# rev1.net
KiCad netlist of a schematic drawn in Altium Designer
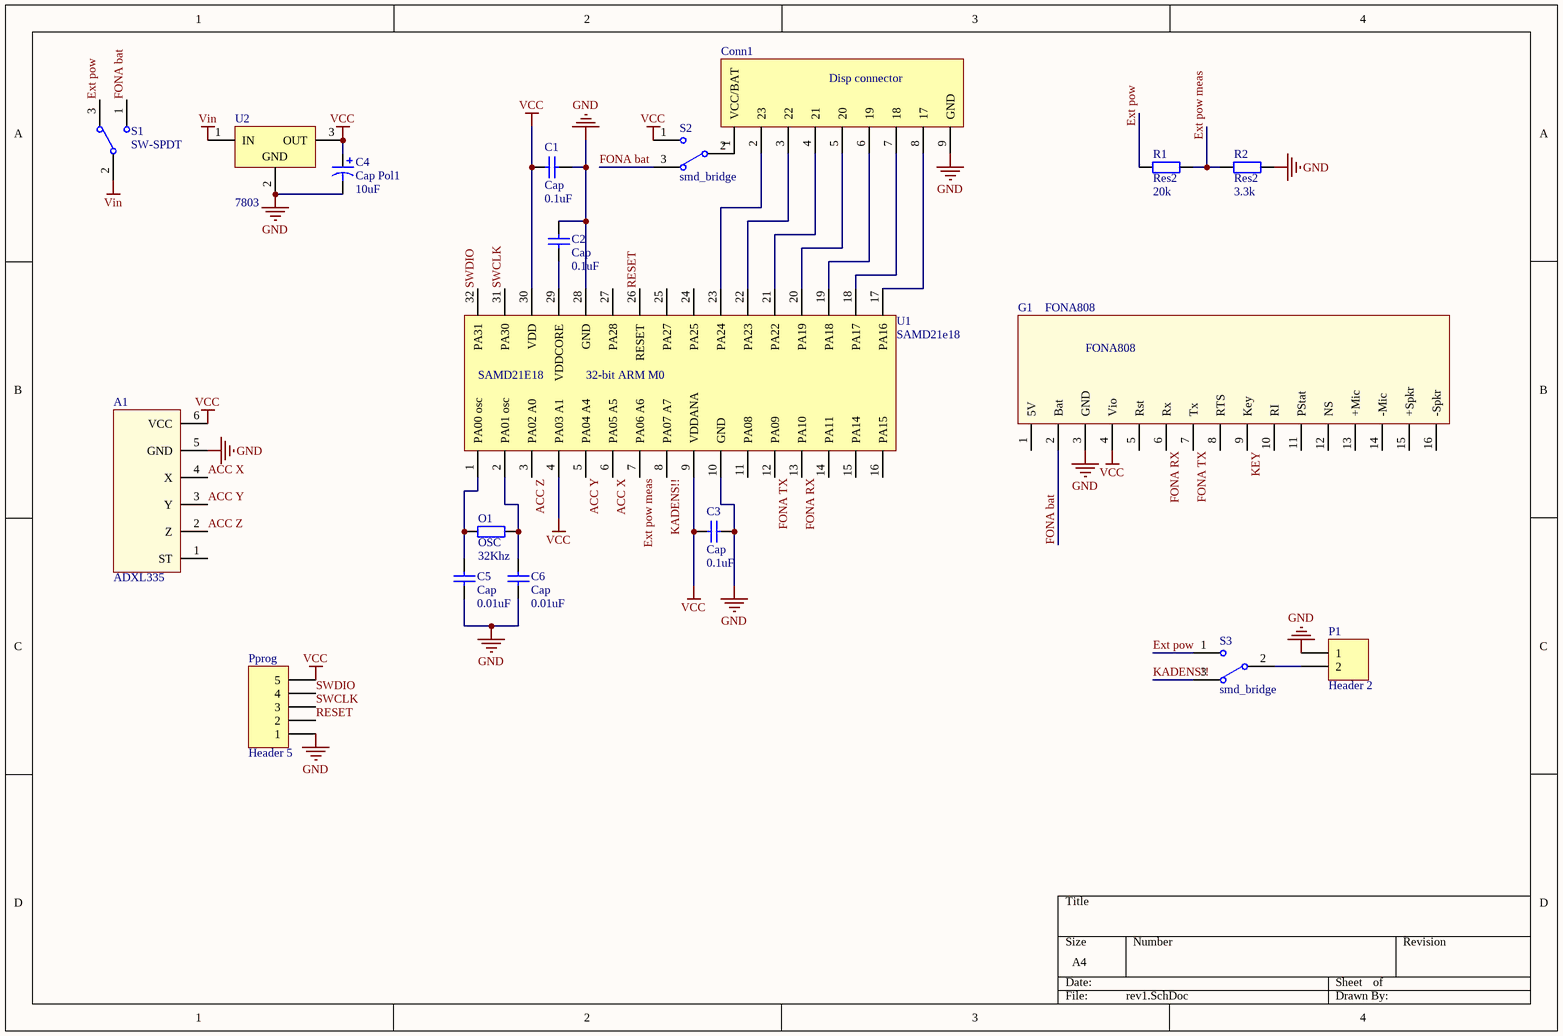
[diagram p0: rev1.SchDoc]

(export (version "E")
  (design (tool "Eeschema 10.0.6"))
  (components
    (comp (ref "A1") (value "ADXL335") (footprint "ADXL") (libsource (lib "Schlib1") (part "ADXL335")))
    (comp (ref "C1")
      (value "Cap")
      (footprint "R3216-1206")
      (description "Capacitor")
      (fields (field (name "ALTIUM_VALUE") "0.1uF") (field (name "PUBLISHER") "Altium Limited"))
      (libsource (lib "Miscellaneous Devices") (part "Cap"))
    )
    (comp (ref "C2")
      (value "Cap")
      (footprint "R3216-1206")
      (description "Capacitor")
      (fields (field (name "ALTIUM_VALUE") "0.1uF") (field (name "PUBLISHER") "Altium Limited"))
      (libsource (lib "Miscellaneous Devices") (part "Cap"))
    )
    (comp (ref "C3")
      (value "Cap")
      (footprint "R3216-1206")
      (description "Capacitor")
      (fields (field (name "ALTIUM_VALUE") "0.1uF") (field (name "PUBLISHER") "Altium Limited"))
      (libsource (lib "Miscellaneous Devices") (part "Cap"))
    )
    (comp (ref "C4")
      (value "Cap Pol1")
      (footprint "RB5-10.5")
      (description "Polarized Capacitor (Radial)")
      (fields (field (name "ALTIUM_VALUE") "10uF") (field (name "PUBLISHER") "Altium Limited"))
      (libsource (lib "Miscellaneous Devices") (part "Cap Pol1"))
    )
    (comp (ref "C5")
      (value "Cap")
      (footprint "R2012-0805")
      (description "Capacitor")
      (fields (field (name "ALTIUM_VALUE") "0.01uF") (field (name "PUBLISHER") "Altium Limited"))
      (libsource (lib "Miscellaneous Devices") (part "Cap"))
    )
    (comp (ref "C6")
      (value "Cap")
      (footprint "R2012-0805")
      (description "Capacitor")
      (fields (field (name "ALTIUM_VALUE") "0.01uF") (field (name "PUBLISHER") "Altium Limited"))
      (libsource (lib "Miscellaneous Devices") (part "Cap"))
    )
    (comp (ref "Conn1")
      (value "Disp connector")
      (footprint "9pin 2.54")
      (libsource (lib "Schlib1") (part "Disp connector"))
    )
    (comp (ref "G1") (value "FONA808") (footprint "FONA808") (libsource (lib "Schlib1") (part "FONA808")))
    (comp (ref "O1")
      (value "OSC")
      (footprint "R2012-0805")
      (description "Resistor")
      (fields (field (name "ALTIUM_VALUE") "32Khz") (field (name "PUBLISHER") "Altium Limited"))
      (libsource (lib "Miscellaneous Devices") (part "Res2"))
    )
    (comp (ref "P1")
      (value "Header 2")
      (footprint "HDR1X2")
      (description "Header, 2-Pin")
      (fields (field (name "PUBLISHER") "Altium Limited"))
      (libsource (lib "Miscellaneous Connectors") (part "Header 2"))
    )
    (comp (ref "Pprog")
      (value "Header 5")
      (footprint "HDR1X5")
      (description "Header, 5-Pin")
      (fields (field (name "PUBLISHER") "Altium Limited"))
      (libsource (lib "Miscellaneous Connectors") (part "Header 5"))
    )
    (comp (ref "R1")
      (value "Res2")
      (footprint "R2012-0805")
      (description "Resistor")
      (fields (field (name "ALTIUM_VALUE") "20k") (field (name "PUBLISHER") "Altium Limited"))
      (libsource (lib "Miscellaneous Devices") (part "Res2"))
    )
    (comp (ref "R2")
      (value "Res2")
      (footprint "R2012-0805")
      (description "Resistor")
      (fields (field (name "ALTIUM_VALUE") "3.3k") (field (name "PUBLISHER") "Altium Limited"))
      (libsource (lib "Miscellaneous Devices") (part "Res2"))
    )
    (comp (ref "S1")
      (value "SW-SPDT")
      (footprint "SW-SPDT2.54mm")
      (description "SPDT Subminiature Toggle Switch, Right Angle Mounting, Vertical Actuation")
      (fields (field (name "PUBLISHER") "Altium Limited"))
      (libsource (lib "Schlib1") (part "SW-SPDT"))
    )
    (comp (ref "S2")
      (value "smd_bridge")
      (footprint "SMD_BRIDGE")
      (libsource (lib "Schlib1") (part "smd_bridge"))
    )
    (comp (ref "S3")
      (value "smd_bridge")
      (footprint "SMD_BRIDGE")
      (libsource (lib "Schlib1") (part "smd_bridge"))
    )
    (comp (ref "U1")
      (value "SAMD21e18")
      (footprint "TQFP32_N")
      (libsource (lib "Schlib1") (part "SAMD21e18"))
    )
    (comp (ref "U2")
      (value "7803")
      (footprint "221A-04")
      (description "3-Terminal Positive Fixed Voltage Regulator")
      (fields (field (name "PUBLISHER") "Altium Limited"))
      (libsource (lib "Schlib1") (part "7803"))
    )
  )
  (nets
    (net (code "1") (name "/ACC X") (class "Default")
      (node (ref "A1") (pin "4") (pinfunction "X_4") (pintype "passive"))
      (node (ref "U1") (pin "6") (pinfunction "PA05_A5_6") (pintype "passive"))
    )
    (net (code "2") (name "/ACC Y") (class "Default")
      (node (ref "A1") (pin "3") (pinfunction "Y_3") (pintype "passive"))
      (node (ref "U1") (pin "5") (pinfunction "PA04_A4_5") (pintype "passive"))
    )
    (net (code "3") (name "/ACC Z") (class "Default")
      (node (ref "A1") (pin "2") (pinfunction "Z_2") (pintype "passive"))
      (node (ref "U1") (pin "3") (pinfunction "PA02_A0_3") (pintype "passive"))
    )
    (net (code "4") (name "/Ext pow") (class "Default")
      (node (ref "R1") (pin "1") (pinfunction "1_1") (pintype "passive"))
      (node (ref "S1") (pin "3") (pinfunction "3_3") (pintype "passive"))
      (node (ref "S3") (pin "1") (pinfunction "1_1") (pintype "passive"))
    )
    (net (code "5") (name "/Ext pow meas") (class "Default")
      (node (ref "R1") (pin "2") (pinfunction "2_2") (pintype "passive"))
      (node (ref "R2") (pin "1") (pinfunction "1_1") (pintype "passive"))
      (node (ref "U1") (pin "7") (pinfunction "PA06_A6_7") (pintype "passive"))
    )
    (net (code "6") (name "/FONA RX") (class "Default")
      (node (ref "G1") (pin "6") (pinfunction "Rx_6") (pintype "passive"))
      (node (ref "U1") (pin "13") (pinfunction "PA10_13") (pintype "passive"))
    )
    (net (code "7") (name "/FONA TX") (class "Default")
      (node (ref "G1") (pin "7") (pinfunction "Tx_7") (pintype "passive"))
      (node (ref "U1") (pin "12") (pinfunction "PA09_12") (pintype "passive"))
    )
    (net (code "8") (name "/FONA bat") (class "Default")
      (node (ref "G1") (pin "2") (pinfunction "Bat_2") (pintype "passive"))
      (node (ref "S1") (pin "1") (pinfunction "1_1") (pintype "passive"))
      (node (ref "S2") (pin "3") (pinfunction "3_3") (pintype "passive"))
    )
    (net (code "9") (name "/KADENS!!") (class "Default")
      (node (ref "S3") (pin "3") (pinfunction "3_3") (pintype "passive"))
      (node (ref "U1") (pin "8") (pinfunction "PA07_A7_8") (pintype "passive"))
    )
    (net (code "10") (name "/KEY") (class "Default")
      (node (ref "G1") (pin "9") (pinfunction "Key_9") (pintype "passive"))
    )
    (net (code "11") (name "/RESET") (class "Default")
      (node (ref "Pprog") (pin "2") (pinfunction "2_2") (pintype "passive"))
      (node (ref "U1") (pin "26") (pinfunction "RESET_26") (pintype "passive"))
    )
    (net (code "12") (name "/SWCLK") (class "Default")
      (node (ref "Pprog") (pin "3") (pinfunction "3_3") (pintype "passive"))
      (node (ref "U1") (pin "31") (pinfunction "PA30_31") (pintype "passive"))
    )
    (net (code "13") (name "/SWDIO") (class "Default")
      (node (ref "Pprog") (pin "4") (pinfunction "4_4") (pintype "passive"))
      (node (ref "U1") (pin "32") (pinfunction "PA31_32") (pintype "passive"))
    )
    (net (code "14") (name "GND") (class "Default")
      (node (ref "A1") (pin "5") (pinfunction "GND_5") (pintype "passive"))
      (node (ref "C1") (pin "1") (pinfunction "1_1") (pintype "passive"))
      (node (ref "C2") (pin "2") (pinfunction "2_2") (pintype "passive"))
      (node (ref "C3") (pin "1") (pinfunction "1_1") (pintype "passive"))
      (node (ref "C4") (pin "2") (pinfunction "2_2") (pintype "passive"))
      (node (ref "C5") (pin "1") (pinfunction "1_1") (pintype "passive"))
      (node (ref "C6") (pin "1") (pinfunction "1_1") (pintype "passive"))
      (node (ref "Conn1") (pin "9") (pinfunction "GND_9") (pintype "passive"))
      (node (ref "G1") (pin "3") (pinfunction "GND_3") (pintype "passive"))
      (node (ref "P1") (pin "1") (pinfunction "1_1") (pintype "passive"))
      (node (ref "Pprog") (pin "1") (pinfunction "1_1") (pintype "passive"))
      (node (ref "R2") (pin "2") (pinfunction "2_2") (pintype "passive"))
      (node (ref "U1") (pin "10") (pinfunction "GND_10") (pintype "passive"))
      (node (ref "U1") (pin "28") (pinfunction "GND_28") (pintype "passive"))
      (node (ref "U2") (pin "2") (pinfunction "GND_2") (pintype "power_in"))
    )
    (net (code "15") (name "Net-(Conn1-17)") (class "Default")
      (node (ref "Conn1") (pin "8") (pinfunction "17_8") (pintype "passive"))
      (node (ref "U1") (pin "17") (pinfunction "PA16_17") (pintype "passive"))
    )
    (net (code "16") (name "Net-(Conn1-18)") (class "Default")
      (node (ref "Conn1") (pin "7") (pinfunction "18_7") (pintype "passive"))
      (node (ref "U1") (pin "18") (pinfunction "PA17_18") (pintype "passive"))
    )
    (net (code "17") (name "Net-(Conn1-19)") (class "Default")
      (node (ref "Conn1") (pin "6") (pinfunction "19_6") (pintype "passive"))
      (node (ref "U1") (pin "19") (pinfunction "PA18_19") (pintype "passive"))
    )
    (net (code "18") (name "Net-(Conn1-20)") (class "Default")
      (node (ref "Conn1") (pin "5") (pinfunction "20_5") (pintype "passive"))
      (node (ref "U1") (pin "20") (pinfunction "PA19_20") (pintype "passive"))
    )
    (net (code "19") (name "Net-(Conn1-21)") (class "Default")
      (node (ref "Conn1") (pin "4") (pinfunction "21_4") (pintype "passive"))
      (node (ref "U1") (pin "21") (pinfunction "PA22_21") (pintype "passive"))
    )
    (net (code "20") (name "Net-(Conn1-22)") (class "Default")
      (node (ref "Conn1") (pin "3") (pinfunction "22_3") (pintype "passive"))
      (node (ref "U1") (pin "22") (pinfunction "PA23_22") (pintype "passive"))
    )
    (net (code "21") (name "Net-(Conn1-23)") (class "Default")
      (node (ref "Conn1") (pin "2") (pinfunction "23_2") (pintype "passive"))
      (node (ref "U1") (pin "23") (pinfunction "PA24_23") (pintype "passive"))
    )
    (net (code "22") (name "Net-(Conn1-VCC{slash}BAT)") (class "Default")
      (node (ref "Conn1") (pin "1") (pinfunction "VCC/BAT_1") (pintype "passive"))
      (node (ref "S2") (pin "2") (pinfunction "2_2") (pintype "passive"))
    )
    (net (code "23") (name "Net-(P1-Pad2)") (class "Default")
      (node (ref "P1") (pin "2") (pinfunction "2_2") (pintype "passive"))
      (node (ref "S3") (pin "2") (pinfunction "2_2") (pintype "passive"))
    )
    (net (code "24") (name "Net-(U1-PA00_osc)") (class "Default")
      (node (ref "C5") (pin "2") (pinfunction "2_2") (pintype "passive"))
      (node (ref "O1") (pin "1") (pinfunction "1_1") (pintype "passive"))
      (node (ref "U1") (pin "1") (pinfunction "PA00_osc_1") (pintype "passive"))
    )
    (net (code "25") (name "Net-(U1-PA01_osc)") (class "Default")
      (node (ref "C6") (pin "2") (pinfunction "2_2") (pintype "passive"))
      (node (ref "O1") (pin "2") (pinfunction "2_2") (pintype "passive"))
      (node (ref "U1") (pin "2") (pinfunction "PA01_osc_2") (pintype "passive"))
    )
    (net (code "26") (name "Net-(U1-VDDCORE)") (class "Default")
      (node (ref "C2") (pin "1") (pinfunction "1_1") (pintype "passive"))
      (node (ref "U1") (pin "29") (pinfunction "VDDCORE_29") (pintype "passive"))
    )
    (net (code "27") (name "VCC") (class "Default")
      (node (ref "A1") (pin "6") (pinfunction "VCC_6") (pintype "passive"))
      (node (ref "C1") (pin "2") (pinfunction "2_2") (pintype "passive"))
      (node (ref "C3") (pin "2") (pinfunction "2_2") (pintype "passive"))
      (node (ref "C4") (pin "1") (pinfunction "1_1") (pintype "passive"))
      (node (ref "G1") (pin "4") (pinfunction "Vio_4") (pintype "passive"))
      (node (ref "Pprog") (pin "5") (pinfunction "5_5") (pintype "passive"))
      (node (ref "S2") (pin "1") (pinfunction "1_1") (pintype "passive"))
      (node (ref "U1") (pin "30") (pinfunction "VDD_30") (pintype "passive"))
      (node (ref "U1") (pin "4") (pinfunction "PA03_A1_4") (pintype "passive"))
      (node (ref "U1") (pin "9") (pinfunction "VDDANA_9") (pintype "passive"))
      (node (ref "U2") (pin "3") (pinfunction "OUT_3") (pintype "power_in"))
    )
    (net (code "28") (name "Vin") (class "Default")
      (node (ref "S1") (pin "2") (pinfunction "2_2") (pintype "passive"))
      (node (ref "U2") (pin "1") (pinfunction "IN_1") (pintype "power_in"))
    )
    (net (code "29") (name "unconnected-(A1-ST-Pad1)") (class "Default")
      (node (ref "A1") (pin "1") (pinfunction "ST_1") (pintype "passive"))
    )
    (net (code "30") (name "unconnected-(G1-+Mic-Pad13)") (class "Default")
      (node (ref "G1") (pin "13") (pinfunction "+Mic_13") (pintype "passive"))
    )
    (net (code "31") (name "unconnected-(G1-+Spkr-Pad15)") (class "Default")
      (node (ref "G1") (pin "15") (pinfunction "+Spkr_15") (pintype "passive"))
    )
    (net (code "32") (name "unconnected-(G1--Mic-Pad14)") (class "Default")
      (node (ref "G1") (pin "14") (pinfunction "-Mic_14") (pintype "passive"))
    )
    (net (code "33") (name "unconnected-(G1--Spkr-Pad16)") (class "Default")
      (node (ref "G1") (pin "16") (pinfunction "-Spkr_16") (pintype "passive"))
    )
    (net (code "34") (name "unconnected-(G1-5V-Pad1)") (class "Default")
      (node (ref "G1") (pin "1") (pinfunction "5V_1") (pintype "passive"))
    )
    (net (code "35") (name "unconnected-(G1-NS-Pad12)") (class "Default")
      (node (ref "G1") (pin "12") (pinfunction "NS_12") (pintype "passive"))
    )
    (net (code "36") (name "unconnected-(G1-PStat-Pad11)") (class "Default")
      (node (ref "G1") (pin "11") (pinfunction "PStat_11") (pintype "passive"))
    )
    (net (code "37") (name "unconnected-(G1-RI-Pad10)") (class "Default")
      (node (ref "G1") (pin "10") (pinfunction "RI_10") (pintype "passive"))
    )
    (net (code "38") (name "unconnected-(G1-RTS-Pad8)") (class "Default")
      (node (ref "G1") (pin "8") (pinfunction "RTS_8") (pintype "passive"))
    )
    (net (code "39") (name "unconnected-(G1-Rst-Pad5)") (class "Default")
      (node (ref "G1") (pin "5") (pinfunction "Rst_5") (pintype "passive"))
    )
    (net (code "40") (name "unconnected-(U1-PA08-Pad11)") (class "Default")
      (node (ref "U1") (pin "11") (pinfunction "PA08_11") (pintype "passive"))
    )
    (net (code "41") (name "unconnected-(U1-PA11-Pad14)") (class "Default")
      (node (ref "U1") (pin "14") (pinfunction "PA11_14") (pintype "passive"))
    )
    (net (code "42") (name "unconnected-(U1-PA14-Pad15)") (class "Default")
      (node (ref "U1") (pin "15") (pinfunction "PA14_15") (pintype "passive"))
    )
    (net (code "43") (name "unconnected-(U1-PA15-Pad16)") (class "Default")
      (node (ref "U1") (pin "16") (pinfunction "PA15_16") (pintype "passive"))
    )
    (net (code "44") (name "unconnected-(U1-PA25-Pad24)") (class "Default")
      (node (ref "U1") (pin "24") (pinfunction "PA25_24") (pintype "passive"))
    )
    (net (code "45") (name "unconnected-(U1-PA27-Pad25)") (class "Default")
      (node (ref "U1") (pin "25") (pinfunction "PA27_25") (pintype "passive"))
    )
    (net (code "46") (name "unconnected-(U1-PA28-Pad27)") (class "Default")
      (node (ref "U1") (pin "27") (pinfunction "PA28_27") (pintype "passive"))
    )
  )
)
